# sch_cm4_rs485.net
KiCad netlist of a schematic drawn in Altium Designer
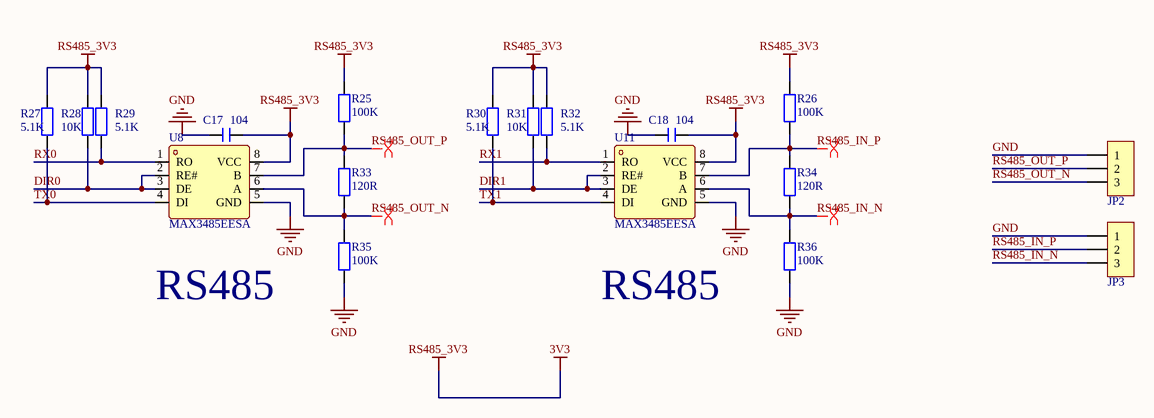
[diagram p0: sch_cm4_rs485.SchDoc]

(export (version "E")
  (design (tool "Eeschema 10.0.6"))
  (components
    (comp (ref "C17")
      (value "104")
      (footprint "C 0805_L")
      (description "贴片电容")
      (libsource (lib "0.1 - 电阻-电容-电感") (part "C"))
    )
    (comp (ref "C18")
      (value "104")
      (footprint "C 0805_L")
      (description "贴片电容")
      (libsource (lib "0.1 - 电阻-电容-电感") (part "C"))
    )
    (comp (ref "JP2")
      (value "HDR-1X3")
      (footprint "KF128-3.81-3P")
      (description "3P接插件")
      (fields (field (name "版权归属") "封装库来自淘宝 ID：黄晶宝石"))
      (libsource (lib "5.6 - 接插件-脚距3.81 (150mil) ") (part "Header 3"))
    )
    (comp (ref "JP3")
      (value "HDR-1X3")
      (footprint "KF128-3.81-3P")
      (description "3P接插件")
      (fields (field (name "版权归属") "封装库来自淘宝 ID：黄晶宝石"))
      (libsource (lib "5.6 - 接插件-脚距3.81 (150mil) ") (part "Header 3"))
    )
    (comp (ref "R25")
      (value "100K")
      (footprint "R 0805_L")
      (description "贴片电阻")
      (fields (field (name "版权归属") "来自淘宝 ID：黄晶宝石"))
      (libsource (lib "0.1 - 电阻-电容-电感") (part "R"))
    )
    (comp (ref "R26")
      (value "100K")
      (footprint "R 0805_L")
      (description "贴片电阻")
      (fields (field (name "版权归属") "来自淘宝 ID：黄晶宝石"))
      (libsource (lib "0.1 - 电阻-电容-电感") (part "R"))
    )
    (comp (ref "R27")
      (value "5.1K")
      (footprint "R 0805_L")
      (description "贴片电阻")
      (fields (field (name "版权归属") "来自淘宝 ID：黄晶宝石"))
      (libsource (lib "0.1 - 电阻-电容-电感") (part "R"))
    )
    (comp (ref "R28")
      (value "10K")
      (footprint "R 0805_L")
      (description "贴片电阻")
      (fields (field (name "版权归属") "来自淘宝 ID：黄晶宝石"))
      (libsource (lib "0.1 - 电阻-电容-电感") (part "R"))
    )
    (comp (ref "R29")
      (value "5.1K")
      (footprint "R 0805_L")
      (description "贴片电阻")
      (fields (field (name "版权归属") "来自淘宝 ID：黄晶宝石"))
      (libsource (lib "0.1 - 电阻-电容-电感") (part "R"))
    )
    (comp (ref "R30")
      (value "5.1K")
      (footprint "R 0805_L")
      (description "贴片电阻")
      (fields (field (name "版权归属") "来自淘宝 ID：黄晶宝石"))
      (libsource (lib "0.1 - 电阻-电容-电感") (part "R"))
    )
    (comp (ref "R31")
      (value "10K")
      (footprint "R 0805_L")
      (description "贴片电阻")
      (fields (field (name "版权归属") "来自淘宝 ID：黄晶宝石"))
      (libsource (lib "0.1 - 电阻-电容-电感") (part "R"))
    )
    (comp (ref "R32")
      (value "5.1K")
      (footprint "R 0805_L")
      (description "贴片电阻")
      (fields (field (name "版权归属") "来自淘宝 ID：黄晶宝石"))
      (libsource (lib "0.1 - 电阻-电容-电感") (part "R"))
    )
    (comp (ref "R33")
      (value "120R")
      (footprint "R 0603_L")
      (description "贴片电阻")
      (fields (field (name "版权归属") "来自淘宝 ID：黄晶宝石"))
      (libsource (lib "0.1 - 电阻-电容-电感") (part "R"))
    )
    (comp (ref "R34")
      (value "120R")
      (footprint "R 0603_L")
      (description "贴片电阻")
      (fields (field (name "版权归属") "来自淘宝 ID：黄晶宝石"))
      (libsource (lib "0.1 - 电阻-电容-电感") (part "R"))
    )
    (comp (ref "R35")
      (value "100K")
      (footprint "R 0805_L")
      (description "贴片电阻")
      (fields (field (name "版权归属") "来自淘宝 ID：黄晶宝石"))
      (libsource (lib "0.1 - 电阻-电容-电感") (part "R"))
    )
    (comp (ref "R36")
      (value "100K")
      (footprint "R 0805_L")
      (description "贴片电阻")
      (fields (field (name "版权归属") "来自淘宝 ID：黄晶宝石"))
      (libsource (lib "0.1 - 电阻-电容-电感") (part "R"))
    )
    (comp (ref "U8")
      (value "MAX3485EESA")
      (footprint "MAX3485EESA")
      (libsource (lib "schlib_cm4") (part "MAX3485EESA"))
    )
    (comp (ref "U11")
      (value "MAX3485EESA")
      (footprint "MAX3485EESA")
      (libsource (lib "schlib_cm4") (part "MAX3485EESA"))
    )
  )
  (nets
    (net (code "1") (name "/DIR0") (class "Default")
      (node (ref "R28") (pin "1") (pinfunction "1_1") (pintype "passive"))
      (node (ref "U8") (pin "2") (pinfunction "RE#_2") (pintype "passive"))
      (node (ref "U8") (pin "3") (pinfunction "DE_3") (pintype "passive"))
    )
    (net (code "2") (name "/DIR1") (class "Default")
      (node (ref "R31") (pin "1") (pinfunction "1_1") (pintype "passive"))
      (node (ref "U11") (pin "2") (pinfunction "RE#_2") (pintype "passive"))
      (node (ref "U11") (pin "3") (pinfunction "DE_3") (pintype "passive"))
    )
    (net (code "3") (name "/RS485_IN_N") (class "Default")
      (node (ref "JP3") (pin "3") (pinfunction "3_3") (pintype "passive"))
      (node (ref "R34") (pin "2") (pinfunction "2_2") (pintype "passive"))
      (node (ref "R36") (pin "1") (pinfunction "1_1") (pintype "passive"))
      (node (ref "U11") (pin "6") (pinfunction "A_6") (pintype "passive"))
    )
    (net (code "4") (name "/RS485_IN_P") (class "Default")
      (node (ref "JP3") (pin "2") (pinfunction "2_2") (pintype "passive"))
      (node (ref "R26") (pin "2") (pinfunction "2_2") (pintype "passive"))
      (node (ref "R34") (pin "1") (pinfunction "1_1") (pintype "passive"))
      (node (ref "U11") (pin "7") (pinfunction "B_7") (pintype "passive"))
    )
    (net (code "5") (name "/RS485_OUT_N") (class "Default")
      (node (ref "JP2") (pin "3") (pinfunction "3_3") (pintype "passive"))
      (node (ref "R33") (pin "2") (pinfunction "2_2") (pintype "passive"))
      (node (ref "R35") (pin "1") (pinfunction "1_1") (pintype "passive"))
      (node (ref "U8") (pin "6") (pinfunction "A_6") (pintype "passive"))
    )
    (net (code "6") (name "/RS485_OUT_P") (class "Default")
      (node (ref "JP2") (pin "2") (pinfunction "2_2") (pintype "passive"))
      (node (ref "R25") (pin "2") (pinfunction "2_2") (pintype "passive"))
      (node (ref "R33") (pin "1") (pinfunction "1_1") (pintype "passive"))
      (node (ref "U8") (pin "7") (pinfunction "B_7") (pintype "passive"))
    )
    (net (code "7") (name "/RX0") (class "Default")
      (node (ref "R29") (pin "1") (pinfunction "1_1") (pintype "passive"))
      (node (ref "U8") (pin "1") (pinfunction "RO_1") (pintype "passive"))
    )
    (net (code "8") (name "/RX1") (class "Default")
      (node (ref "R32") (pin "1") (pinfunction "1_1") (pintype "passive"))
      (node (ref "U11") (pin "1") (pinfunction "RO_1") (pintype "passive"))
    )
    (net (code "9") (name "/TX0") (class "Default")
      (node (ref "R27") (pin "1") (pinfunction "1_1") (pintype "passive"))
      (node (ref "U8") (pin "4") (pinfunction "DI_4") (pintype "passive"))
    )
    (net (code "10") (name "/TX1") (class "Default")
      (node (ref "R30") (pin "1") (pinfunction "1_1") (pintype "passive"))
      (node (ref "U11") (pin "4") (pinfunction "DI_4") (pintype "passive"))
    )
    (net (code "11") (name "3V3") (class "Default")
      (node (ref "C17") (pin "1") (pinfunction "1_1") (pintype "passive"))
      (node (ref "C18") (pin "1") (pinfunction "1_1") (pintype "passive"))
      (node (ref "R25") (pin "1") (pinfunction "1_1") (pintype "passive"))
      (node (ref "R26") (pin "1") (pinfunction "1_1") (pintype "passive"))
      (node (ref "R27") (pin "2") (pinfunction "2_2") (pintype "passive"))
      (node (ref "R28") (pin "2") (pinfunction "2_2") (pintype "passive"))
      (node (ref "R29") (pin "2") (pinfunction "2_2") (pintype "passive"))
      (node (ref "R30") (pin "2") (pinfunction "2_2") (pintype "passive"))
      (node (ref "R31") (pin "2") (pinfunction "2_2") (pintype "passive"))
      (node (ref "R32") (pin "2") (pinfunction "2_2") (pintype "passive"))
      (node (ref "U11") (pin "8") (pinfunction "VCC_8") (pintype "passive"))
      (node (ref "U8") (pin "8") (pinfunction "VCC_8") (pintype "passive"))
    )
    (net (code "12") (name "GND") (class "Default")
      (node (ref "C17") (pin "2") (pinfunction "2_2") (pintype "passive"))
      (node (ref "C18") (pin "2") (pinfunction "2_2") (pintype "passive"))
      (node (ref "JP2") (pin "1") (pinfunction "1_1") (pintype "passive"))
      (node (ref "JP3") (pin "1") (pinfunction "1_1") (pintype "passive"))
      (node (ref "R35") (pin "2") (pinfunction "2_2") (pintype "passive"))
      (node (ref "R36") (pin "2") (pinfunction "2_2") (pintype "passive"))
      (node (ref "U11") (pin "5") (pinfunction "GND_5") (pintype "passive"))
      (node (ref "U8") (pin "5") (pinfunction "GND_5") (pintype "passive"))
    )
  )
)
